# LevelShifter_SCH.net
KiCad netlist of a schematic drawn in Altium Designer
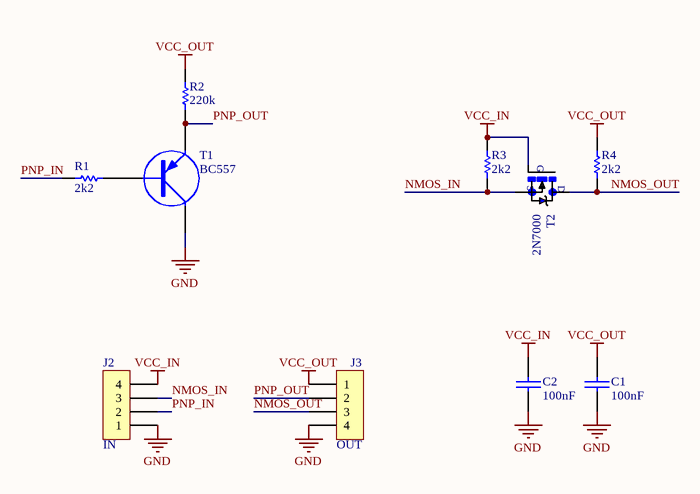
[diagram p0: LevelShifter_SCH.SchDoc]

(export (version "E")
  (design (tool "Eeschema 10.0.6"))
  (components
    (comp (ref "C1") (value "100nF") (footprint "0805") (libsource (lib "LIBEBAL") (part "CAP")))
    (comp (ref "C2") (value "100nF") (footprint "0805") (libsource (lib "LIBEBAL") (part "CAP")))
    (comp (ref "J2") (value "IN") (footprint "SIP4") (libsource (lib "") (part "CON4_1")))
    (comp (ref "J3") (value "OUT") (footprint "SIP4") (libsource (lib "LIBEBAL") (part "CON4")))
    (comp (ref "R1") (value "2k2") (footprint "0805") (libsource (lib "LIBEBAL") (part "RES")))
    (comp (ref "R2") (value "220k") (footprint "0805") (libsource (lib "LIBEBAL") (part "RES")))
    (comp (ref "R3") (value "2k2") (footprint "0805") (libsource (lib "LIBEBAL") (part "RES")))
    (comp (ref "R4") (value "2k2") (footprint "0805") (libsource (lib "LIBEBAL") (part "RES")))
    (comp (ref "T1") (value "BC557") (footprint "TO92") (libsource (lib "LIBEBAL") (part "TRANSISTOR PNP")))
    (comp (ref "T2")
      (value "2N7000")
      (footprint "*TO-92")
      (description "MOSFETs- Power and Small Signal 60V 200mA N-Channel No-Cancel/No-Return")
      (fields (field (name "MF") "STMicroelectronics"))
      (libsource (lib "2N7000") (part "2N7000"))
    )
  )
  (nets
    (net (code "1") (name "/NMOS_IN") (class "Default")
      (node (ref "J2") (pin "3") (pinfunction "3_3") (pintype "passive"))
      (node (ref "R3") (pin "2") (pinfunction "2_2") (pintype "passive"))
      (node (ref "T2") (pin "1") (pinfunction "S_1") (pintype "passive"))
    )
    (net (code "2") (name "/NMOS_OUT") (class "Default")
      (node (ref "J3") (pin "3") (pinfunction "3_3") (pintype "passive"))
      (node (ref "R4") (pin "2") (pinfunction "2_2") (pintype "passive"))
      (node (ref "T2") (pin "3") (pinfunction "D_3") (pintype "passive"))
    )
    (net (code "3") (name "/PNP_IN") (class "Default")
      (node (ref "J2") (pin "2") (pinfunction "2_2") (pintype "passive"))
      (node (ref "R1") (pin "1") (pinfunction "1_1") (pintype "passive"))
    )
    (net (code "4") (name "/PNP_OUT") (class "Default")
      (node (ref "J3") (pin "2") (pinfunction "2_2") (pintype "passive"))
      (node (ref "R2") (pin "2") (pinfunction "2_2") (pintype "passive"))
      (node (ref "T1") (pin "3") (pinfunction "E_3") (pintype "passive"))
    )
    (net (code "5") (name "GND") (class "Default")
      (node (ref "C1") (pin "2") (pinfunction "2_2") (pintype "passive"))
      (node (ref "C2") (pin "2") (pinfunction "2_2") (pintype "passive"))
      (node (ref "J2") (pin "1") (pinfunction "1_1") (pintype "passive"))
      (node (ref "J3") (pin "4") (pinfunction "4_4") (pintype "passive"))
      (node (ref "T1") (pin "2") (pinfunction "C_2") (pintype "passive"))
    )
    (net (code "6") (name "Net-(T1-B)") (class "Default")
      (node (ref "R1") (pin "2") (pinfunction "2_2") (pintype "passive"))
      (node (ref "T1") (pin "1") (pinfunction "B_1") (pintype "passive"))
    )
    (net (code "7") (name "VCC_IN") (class "Default")
      (node (ref "C2") (pin "1") (pinfunction "1_1") (pintype "passive"))
      (node (ref "J2") (pin "4") (pinfunction "4_4") (pintype "passive"))
      (node (ref "R3") (pin "1") (pinfunction "1_1") (pintype "passive"))
      (node (ref "T2") (pin "2") (pinfunction "G_2") (pintype "passive"))
    )
    (net (code "8") (name "VCC_OUT") (class "Default")
      (node (ref "C1") (pin "1") (pinfunction "1_1") (pintype "passive"))
      (node (ref "J3") (pin "1") (pinfunction "1_1") (pintype "passive"))
      (node (ref "R2") (pin "1") (pinfunction "1_1") (pintype "passive"))
      (node (ref "R4") (pin "1") (pinfunction "1_1") (pintype "passive"))
    )
  )
)
